# Micro.net
KiCad netlist of a schematic drawn in EAGLE
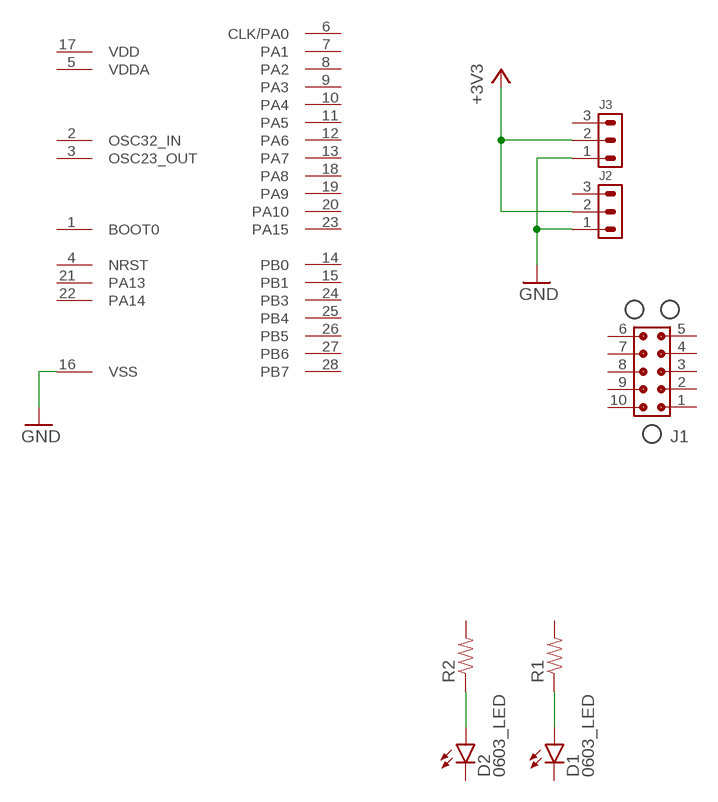
[diagram p0: schematic, sheet 1]

(export (version "E")
  (design (tool "Eeschema 10.0.6"))
  (components
    (comp (ref "D1")
      (value "0603_LED")
      (footprint "eagle-import:0603_LED")
      (libsource (lib "eagle-import") (part "0603_LED"))
    )
    (comp (ref "D2")
      (value "0603_LED")
      (footprint "eagle-import:0603_LED")
      (libsource (lib "eagle-import") (part "0603_LED"))
    )
    (comp (ref "J1")
      (value "TC_2050_IDC_NL_TOP")
      (footprint "eagle-import:TC_2050_IDC_NL_TOP")
      (libsource (lib "eagle-import") (part "TC_2050_IDC_NL_TOP"))
    )
    (comp (ref "J2")
      (value "CONN_3X1_LEAF_SMT_INV")
      (footprint "eagle-import:CONN_3X1_LEAF_SMT_INV")
      (libsource (lib "eagle-import") (part "CONN_3X1_LEAF_SMT_INV"))
    )
    (comp (ref "J3")
      (value "CONN_3X1_LEAF_SMT")
      (footprint "eagle-import:CONN_3X1_LEAF_SMT")
      (libsource (lib "eagle-import") (part "CONN_3X1_LEAF_SMT"))
    )
    (comp (ref "R1")
      (value "0402_RES")
      (footprint "eagle-import:0402")
      (libsource (lib "eagle-import") (part "0402_RES"))
    )
    (comp (ref "R2")
      (value "0402_RES")
      (footprint "eagle-import:0402")
      (libsource (lib "eagle-import") (part "0402_RES"))
    )
    (comp (ref "U1")
      (value "STM32L031G6U6")
      (footprint "eagle-import:STM32_QFN_28_4X4")
      (libsource (lib "eagle-import") (part "STM32L031G6U6"))
    )
  )
  (nets
    (net (code "1") (name "+3V3") (class "Default")
      (node (ref "J2") (pin "2") (pinfunction "2_2") (pintype "bidirectional"))
      (node (ref "J3") (pin "2") (pinfunction "2_2") (pintype "bidirectional"))
    )
    (net (code "2") (name "GND") (class "Default")
      (node (ref "J2") (pin "1") (pinfunction "1_1") (pintype "bidirectional"))
      (node (ref "J3") (pin "1") (pinfunction "1_1") (pintype "bidirectional"))
      (node (ref "U1") (pin "16") (pinfunction "VSS_16") (pintype "bidirectional"))
    )
    (net (code "3") (name "Net-(D1-A)") (class "Default")
      (node (ref "D1") (pin "P$1") (pinfunction "A_P$1") (pintype "passive"))
      (node (ref "R1") (pin "P$1") (pinfunction "1_P$1") (pintype "passive"))
    )
    (net (code "4") (name "Net-(D2-A)") (class "Default")
      (node (ref "D2") (pin "P$1") (pinfunction "A_P$1") (pintype "passive"))
      (node (ref "R2") (pin "P$1") (pinfunction "1_P$1") (pintype "passive"))
    )
    (net (code "5") (name "unconnected-(D1-C-PadP$2)") (class "Default")
      (node (ref "D1") (pin "P$2") (pinfunction "C_P$2") (pintype "passive"))
    )
    (net (code "6") (name "unconnected-(D2-C-PadP$2)") (class "Default")
      (node (ref "D2") (pin "P$2") (pinfunction "C_P$2") (pintype "passive"))
    )
    (net (code "7") (name "unconnected-(J1-Pad1)") (class "Default")
      (node (ref "J1") (pin "1") (pinfunction "1_1") (pintype "bidirectional"))
    )
    (net (code "8") (name "unconnected-(J1-Pad2)") (class "Default")
      (node (ref "J1") (pin "2") (pinfunction "2_2") (pintype "bidirectional"))
    )
    (net (code "9") (name "unconnected-(J1-Pad3)") (class "Default")
      (node (ref "J1") (pin "3") (pinfunction "3_3") (pintype "bidirectional"))
    )
    (net (code "10") (name "unconnected-(J1-Pad4)") (class "Default")
      (node (ref "J1") (pin "4") (pinfunction "4_4") (pintype "bidirectional"))
    )
    (net (code "11") (name "unconnected-(J1-Pad5)") (class "Default")
      (node (ref "J1") (pin "5") (pinfunction "5_5") (pintype "bidirectional"))
    )
    (net (code "12") (name "unconnected-(J1-Pad6)") (class "Default")
      (node (ref "J1") (pin "6") (pinfunction "6_6") (pintype "bidirectional"))
    )
    (net (code "13") (name "unconnected-(J1-Pad7)") (class "Default")
      (node (ref "J1") (pin "7") (pinfunction "7_7") (pintype "bidirectional"))
    )
    (net (code "14") (name "unconnected-(J1-Pad8)") (class "Default")
      (node (ref "J1") (pin "8") (pinfunction "8_8") (pintype "bidirectional"))
    )
    (net (code "15") (name "unconnected-(J1-Pad9)") (class "Default")
      (node (ref "J1") (pin "9") (pinfunction "9_9") (pintype "bidirectional"))
    )
    (net (code "16") (name "unconnected-(J1-Pad10)") (class "Default")
      (node (ref "J1") (pin "10") (pinfunction "10_10") (pintype "bidirectional"))
    )
    (net (code "17") (name "unconnected-(J2-Pad3)") (class "Default")
      (node (ref "J2") (pin "3") (pinfunction "3_3") (pintype "bidirectional"))
    )
    (net (code "18") (name "unconnected-(J3-Pad3)") (class "Default")
      (node (ref "J3") (pin "3") (pinfunction "3_3") (pintype "bidirectional"))
    )
    (net (code "19") (name "unconnected-(R1-2-PadP$2)") (class "Default")
      (node (ref "R1") (pin "P$2") (pinfunction "2_P$2") (pintype "passive"))
    )
    (net (code "20") (name "unconnected-(R2-2-PadP$2)") (class "Default")
      (node (ref "R2") (pin "P$2") (pinfunction "2_P$2") (pintype "passive"))
    )
    (net (code "21") (name "unconnected-(U1-BOOT0-Pad1)") (class "Default")
      (node (ref "U1") (pin "1") (pinfunction "BOOT0_1") (pintype "bidirectional"))
    )
    (net (code "22") (name "unconnected-(U1-CLK{slash}PA0-Pad6)") (class "Default")
      (node (ref "U1") (pin "6") (pinfunction "CLK/PA0_6") (pintype "bidirectional"))
    )
    (net (code "23") (name "unconnected-(U1-NRST-Pad4)") (class "Default")
      (node (ref "U1") (pin "4") (pinfunction "NRST_4") (pintype "bidirectional"))
    )
    (net (code "24") (name "unconnected-(U1-OSC23_OUT-Pad3)") (class "Default")
      (node (ref "U1") (pin "3") (pinfunction "OSC23_OUT_3") (pintype "bidirectional"))
    )
    (net (code "25") (name "unconnected-(U1-OSC32_IN-Pad2)") (class "Default")
      (node (ref "U1") (pin "2") (pinfunction "OSC32_IN_2") (pintype "bidirectional"))
    )
    (net (code "26") (name "unconnected-(U1-PA1-Pad7)") (class "Default")
      (node (ref "U1") (pin "7") (pinfunction "PA1_7") (pintype "bidirectional"))
    )
    (net (code "27") (name "unconnected-(U1-PA2-Pad8)") (class "Default")
      (node (ref "U1") (pin "8") (pinfunction "PA2_8") (pintype "bidirectional"))
    )
    (net (code "28") (name "unconnected-(U1-PA3-Pad9)") (class "Default")
      (node (ref "U1") (pin "9") (pinfunction "PA3_9") (pintype "bidirectional"))
    )
    (net (code "29") (name "unconnected-(U1-PA4-Pad10)") (class "Default")
      (node (ref "U1") (pin "10") (pinfunction "PA4_10") (pintype "bidirectional"))
    )
    (net (code "30") (name "unconnected-(U1-PA5-Pad11)") (class "Default")
      (node (ref "U1") (pin "11") (pinfunction "PA5_11") (pintype "bidirectional"))
    )
    (net (code "31") (name "unconnected-(U1-PA6-Pad12)") (class "Default")
      (node (ref "U1") (pin "12") (pinfunction "PA6_12") (pintype "bidirectional"))
    )
    (net (code "32") (name "unconnected-(U1-PA7-Pad13)") (class "Default")
      (node (ref "U1") (pin "13") (pinfunction "PA7_13") (pintype "bidirectional"))
    )
    (net (code "33") (name "unconnected-(U1-PA8-Pad18)") (class "Default")
      (node (ref "U1") (pin "18") (pinfunction "PA8_18") (pintype "bidirectional"))
    )
    (net (code "34") (name "unconnected-(U1-PA9-Pad19)") (class "Default")
      (node (ref "U1") (pin "19") (pinfunction "PA9_19") (pintype "bidirectional"))
    )
    (net (code "35") (name "unconnected-(U1-PA10-Pad20)") (class "Default")
      (node (ref "U1") (pin "20") (pinfunction "PA10_20") (pintype "bidirectional"))
    )
    (net (code "36") (name "unconnected-(U1-PA13-Pad21)") (class "Default")
      (node (ref "U1") (pin "21") (pinfunction "PA13_21") (pintype "bidirectional"))
    )
    (net (code "37") (name "unconnected-(U1-PA14-Pad22)") (class "Default")
      (node (ref "U1") (pin "22") (pinfunction "PA14_22") (pintype "bidirectional"))
    )
    (net (code "38") (name "unconnected-(U1-PA15-Pad23)") (class "Default")
      (node (ref "U1") (pin "23") (pinfunction "PA15_23") (pintype "bidirectional"))
    )
    (net (code "39") (name "unconnected-(U1-PB0-Pad14)") (class "Default")
      (node (ref "U1") (pin "14") (pinfunction "PB0_14") (pintype "bidirectional"))
    )
    (net (code "40") (name "unconnected-(U1-PB1-Pad15)") (class "Default")
      (node (ref "U1") (pin "15") (pinfunction "PB1_15") (pintype "bidirectional"))
    )
    (net (code "41") (name "unconnected-(U1-PB3-Pad24)") (class "Default")
      (node (ref "U1") (pin "24") (pinfunction "PB3_24") (pintype "bidirectional"))
    )
    (net (code "42") (name "unconnected-(U1-PB4-Pad25)") (class "Default")
      (node (ref "U1") (pin "25") (pinfunction "PB4_25") (pintype "bidirectional"))
    )
    (net (code "43") (name "unconnected-(U1-PB5-Pad26)") (class "Default")
      (node (ref "U1") (pin "26") (pinfunction "PB5_26") (pintype "bidirectional"))
    )
    (net (code "44") (name "unconnected-(U1-PB6-Pad27)") (class "Default")
      (node (ref "U1") (pin "27") (pinfunction "PB6_27") (pintype "bidirectional"))
    )
    (net (code "45") (name "unconnected-(U1-PB7-Pad28)") (class "Default")
      (node (ref "U1") (pin "28") (pinfunction "PB7_28") (pintype "bidirectional"))
    )
    (net (code "46") (name "unconnected-(U1-VDD-Pad17)") (class "Default")
      (node (ref "U1") (pin "17") (pinfunction "VDD_17") (pintype "bidirectional"))
    )
    (net (code "47") (name "unconnected-(U1-VDDA-Pad5)") (class "Default")
      (node (ref "U1") (pin "5") (pinfunction "VDDA_5") (pintype "bidirectional"))
    )
  )
)
